# led_2835_driver_circle_10X10cm.net
KiCad netlist of a schematic drawn in Altium Designer
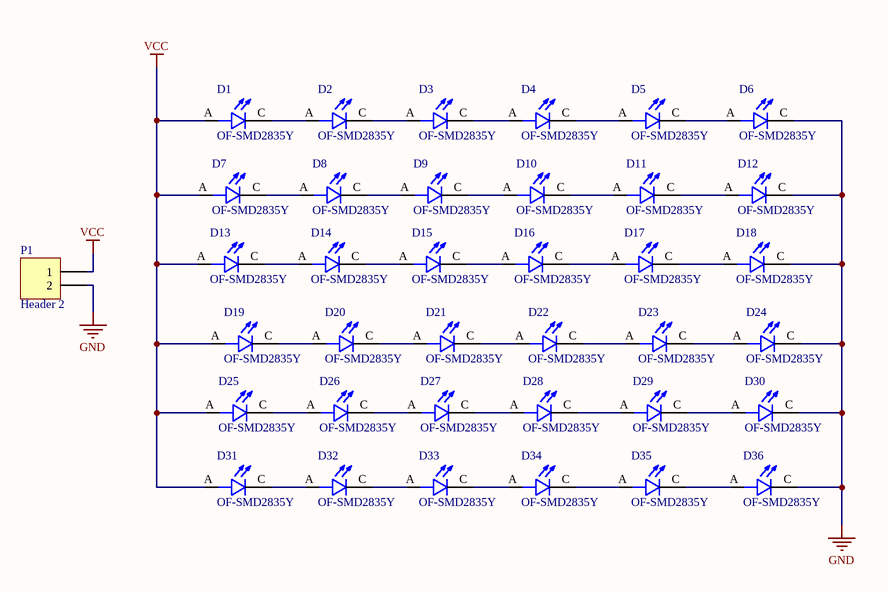
[diagram p0: led_2835_driver_circle_10X10cm.SchDoc]

(export (version "E")
  (design (tool "Eeschema 10.0.6"))
  (components
    (comp (ref "D1")
      (value "OF-SMD2835Y")
      (footprint "LED_OF-SMD2835Y")
      (description "LED; SMD; 2835, PLCC2; yellow; 2200-2800mcd; 2.8x3.5x0.75mm; 120Â°")
      (libsource (lib "") (part "OF-SMD2835Y_1"))
    )
    (comp (ref "D2")
      (value "OF-SMD2835Y")
      (footprint "LED_OF-SMD2835Y")
      (description "LED; SMD; 2835, PLCC2; yellow; 2200-2800mcd; 2.8x3.5x0.75mm; 120Â°")
      (libsource (lib "OF-SMD2835Y") (part "OF-SMD2835Y"))
    )
    (comp (ref "D3")
      (value "OF-SMD2835Y")
      (footprint "LED_OF-SMD2835Y")
      (description "LED; SMD; 2835, PLCC2; yellow; 2200-2800mcd; 2.8x3.5x0.75mm; 120Â°")
      (libsource (lib "OF-SMD2835Y") (part "OF-SMD2835Y"))
    )
    (comp (ref "D4")
      (value "OF-SMD2835Y")
      (footprint "LED_OF-SMD2835Y")
      (description "LED; SMD; 2835, PLCC2; yellow; 2200-2800mcd; 2.8x3.5x0.75mm; 120Â°")
      (libsource (lib "OF-SMD2835Y") (part "OF-SMD2835Y"))
    )
    (comp (ref "D5")
      (value "OF-SMD2835Y")
      (footprint "LED_OF-SMD2835Y")
      (description "LED; SMD; 2835, PLCC2; yellow; 2200-2800mcd; 2.8x3.5x0.75mm; 120Â°")
      (libsource (lib "OF-SMD2835Y") (part "OF-SMD2835Y"))
    )
    (comp (ref "D6")
      (value "OF-SMD2835Y")
      (footprint "LED_OF-SMD2835Y")
      (description "LED; SMD; 2835, PLCC2; yellow; 2200-2800mcd; 2.8x3.5x0.75mm; 120Â°")
      (libsource (lib "OF-SMD2835Y") (part "OF-SMD2835Y"))
    )
    (comp (ref "D7")
      (value "OF-SMD2835Y")
      (footprint "LED_OF-SMD2835Y")
      (description "LED; SMD; 2835, PLCC2; yellow; 2200-2800mcd; 2.8x3.5x0.75mm; 120Â°")
      (libsource (lib "") (part "OF-SMD2835Y_1"))
    )
    (comp (ref "D8")
      (value "OF-SMD2835Y")
      (footprint "LED_OF-SMD2835Y")
      (description "LED; SMD; 2835, PLCC2; yellow; 2200-2800mcd; 2.8x3.5x0.75mm; 120Â°")
      (libsource (lib "OF-SMD2835Y") (part "OF-SMD2835Y"))
    )
    (comp (ref "D9")
      (value "OF-SMD2835Y")
      (footprint "LED_OF-SMD2835Y")
      (description "LED; SMD; 2835, PLCC2; yellow; 2200-2800mcd; 2.8x3.5x0.75mm; 120Â°")
      (libsource (lib "OF-SMD2835Y") (part "OF-SMD2835Y"))
    )
    (comp (ref "D10")
      (value "OF-SMD2835Y")
      (footprint "LED_OF-SMD2835Y")
      (description "LED; SMD; 2835, PLCC2; yellow; 2200-2800mcd; 2.8x3.5x0.75mm; 120Â°")
      (libsource (lib "OF-SMD2835Y") (part "OF-SMD2835Y"))
    )
    (comp (ref "D11")
      (value "OF-SMD2835Y")
      (footprint "LED_OF-SMD2835Y")
      (description "LED; SMD; 2835, PLCC2; yellow; 2200-2800mcd; 2.8x3.5x0.75mm; 120Â°")
      (libsource (lib "OF-SMD2835Y") (part "OF-SMD2835Y"))
    )
    (comp (ref "D12")
      (value "OF-SMD2835Y")
      (footprint "LED_OF-SMD2835Y")
      (description "LED; SMD; 2835, PLCC2; yellow; 2200-2800mcd; 2.8x3.5x0.75mm; 120Â°")
      (libsource (lib "OF-SMD2835Y") (part "OF-SMD2835Y"))
    )
    (comp (ref "D13")
      (value "OF-SMD2835Y")
      (footprint "LED_OF-SMD2835Y")
      (description "LED; SMD; 2835, PLCC2; yellow; 2200-2800mcd; 2.8x3.5x0.75mm; 120Â°")
      (libsource (lib "") (part "OF-SMD2835Y_1"))
    )
    (comp (ref "D14")
      (value "OF-SMD2835Y")
      (footprint "LED_OF-SMD2835Y")
      (description "LED; SMD; 2835, PLCC2; yellow; 2200-2800mcd; 2.8x3.5x0.75mm; 120Â°")
      (libsource (lib "") (part "OF-SMD2835Y_1"))
    )
    (comp (ref "D15")
      (value "OF-SMD2835Y")
      (footprint "LED_OF-SMD2835Y")
      (description "LED; SMD; 2835, PLCC2; yellow; 2200-2800mcd; 2.8x3.5x0.75mm; 120Â°")
      (libsource (lib "OF-SMD2835Y") (part "OF-SMD2835Y"))
    )
    (comp (ref "D16")
      (value "OF-SMD2835Y")
      (footprint "LED_OF-SMD2835Y")
      (description "LED; SMD; 2835, PLCC2; yellow; 2200-2800mcd; 2.8x3.5x0.75mm; 120Â°")
      (libsource (lib "OF-SMD2835Y") (part "OF-SMD2835Y"))
    )
    (comp (ref "D17")
      (value "OF-SMD2835Y")
      (footprint "LED_OF-SMD2835Y")
      (description "LED; SMD; 2835, PLCC2; yellow; 2200-2800mcd; 2.8x3.5x0.75mm; 120Â°")
      (libsource (lib "OF-SMD2835Y") (part "OF-SMD2835Y"))
    )
    (comp (ref "D18")
      (value "OF-SMD2835Y")
      (footprint "LED_OF-SMD2835Y")
      (description "LED; SMD; 2835, PLCC2; yellow; 2200-2800mcd; 2.8x3.5x0.75mm; 120Â°")
      (libsource (lib "OF-SMD2835Y") (part "OF-SMD2835Y"))
    )
    (comp (ref "D19")
      (value "OF-SMD2835Y")
      (footprint "LED_OF-SMD2835Y")
      (description "LED; SMD; 2835, PLCC2; yellow; 2200-2800mcd; 2.8x3.5x0.75mm; 120Â°")
      (libsource (lib "") (part "OF-SMD2835Y_1"))
    )
    (comp (ref "D20")
      (value "OF-SMD2835Y")
      (footprint "LED_OF-SMD2835Y")
      (description "LED; SMD; 2835, PLCC2; yellow; 2200-2800mcd; 2.8x3.5x0.75mm; 120Â°")
      (libsource (lib "OF-SMD2835Y") (part "OF-SMD2835Y"))
    )
    (comp (ref "D21")
      (value "OF-SMD2835Y")
      (footprint "LED_OF-SMD2835Y")
      (description "LED; SMD; 2835, PLCC2; yellow; 2200-2800mcd; 2.8x3.5x0.75mm; 120Â°")
      (libsource (lib "OF-SMD2835Y") (part "OF-SMD2835Y"))
    )
    (comp (ref "D22")
      (value "OF-SMD2835Y")
      (footprint "LED_OF-SMD2835Y")
      (description "LED; SMD; 2835, PLCC2; yellow; 2200-2800mcd; 2.8x3.5x0.75mm; 120Â°")
      (libsource (lib "OF-SMD2835Y") (part "OF-SMD2835Y"))
    )
    (comp (ref "D23")
      (value "OF-SMD2835Y")
      (footprint "LED_OF-SMD2835Y")
      (description "LED; SMD; 2835, PLCC2; yellow; 2200-2800mcd; 2.8x3.5x0.75mm; 120Â°")
      (libsource (lib "OF-SMD2835Y") (part "OF-SMD2835Y"))
    )
    (comp (ref "D24")
      (value "OF-SMD2835Y")
      (footprint "LED_OF-SMD2835Y")
      (description "LED; SMD; 2835, PLCC2; yellow; 2200-2800mcd; 2.8x3.5x0.75mm; 120Â°")
      (libsource (lib "OF-SMD2835Y") (part "OF-SMD2835Y"))
    )
    (comp (ref "D25")
      (value "OF-SMD2835Y")
      (footprint "LED_OF-SMD2835Y")
      (description "LED; SMD; 2835, PLCC2; yellow; 2200-2800mcd; 2.8x3.5x0.75mm; 120Â°")
      (libsource (lib "") (part "OF-SMD2835Y_1"))
    )
    (comp (ref "D26")
      (value "OF-SMD2835Y")
      (footprint "LED_OF-SMD2835Y")
      (description "LED; SMD; 2835, PLCC2; yellow; 2200-2800mcd; 2.8x3.5x0.75mm; 120Â°")
      (libsource (lib "OF-SMD2835Y") (part "OF-SMD2835Y"))
    )
    (comp (ref "D27")
      (value "OF-SMD2835Y")
      (footprint "LED_OF-SMD2835Y")
      (description "LED; SMD; 2835, PLCC2; yellow; 2200-2800mcd; 2.8x3.5x0.75mm; 120Â°")
      (libsource (lib "OF-SMD2835Y") (part "OF-SMD2835Y"))
    )
    (comp (ref "D28")
      (value "OF-SMD2835Y")
      (footprint "LED_OF-SMD2835Y")
      (description "LED; SMD; 2835, PLCC2; yellow; 2200-2800mcd; 2.8x3.5x0.75mm; 120Â°")
      (libsource (lib "OF-SMD2835Y") (part "OF-SMD2835Y"))
    )
    (comp (ref "D29")
      (value "OF-SMD2835Y")
      (footprint "LED_OF-SMD2835Y")
      (description "LED; SMD; 2835, PLCC2; yellow; 2200-2800mcd; 2.8x3.5x0.75mm; 120Â°")
      (libsource (lib "OF-SMD2835Y") (part "OF-SMD2835Y"))
    )
    (comp (ref "D30")
      (value "OF-SMD2835Y")
      (footprint "LED_OF-SMD2835Y")
      (description "LED; SMD; 2835, PLCC2; yellow; 2200-2800mcd; 2.8x3.5x0.75mm; 120Â°")
      (libsource (lib "OF-SMD2835Y") (part "OF-SMD2835Y"))
    )
    (comp (ref "D31")
      (value "OF-SMD2835Y")
      (footprint "LED_OF-SMD2835Y")
      (description "LED; SMD; 2835, PLCC2; yellow; 2200-2800mcd; 2.8x3.5x0.75mm; 120Â°")
      (libsource (lib "") (part "OF-SMD2835Y_1"))
    )
    (comp (ref "D32")
      (value "OF-SMD2835Y")
      (footprint "LED_OF-SMD2835Y")
      (description "LED; SMD; 2835, PLCC2; yellow; 2200-2800mcd; 2.8x3.5x0.75mm; 120Â°")
      (libsource (lib "OF-SMD2835Y") (part "OF-SMD2835Y"))
    )
    (comp (ref "D33")
      (value "OF-SMD2835Y")
      (footprint "LED_OF-SMD2835Y")
      (description "LED; SMD; 2835, PLCC2; yellow; 2200-2800mcd; 2.8x3.5x0.75mm; 120Â°")
      (libsource (lib "OF-SMD2835Y") (part "OF-SMD2835Y"))
    )
    (comp (ref "D34")
      (value "OF-SMD2835Y")
      (footprint "LED_OF-SMD2835Y")
      (description "LED; SMD; 2835, PLCC2; yellow; 2200-2800mcd; 2.8x3.5x0.75mm; 120Â°")
      (libsource (lib "OF-SMD2835Y") (part "OF-SMD2835Y"))
    )
    (comp (ref "D35")
      (value "OF-SMD2835Y")
      (footprint "LED_OF-SMD2835Y")
      (description "LED; SMD; 2835, PLCC2; yellow; 2200-2800mcd; 2.8x3.5x0.75mm; 120Â°")
      (libsource (lib "OF-SMD2835Y") (part "OF-SMD2835Y"))
    )
    (comp (ref "D36")
      (value "OF-SMD2835Y")
      (footprint "LED_OF-SMD2835Y")
      (description "LED; SMD; 2835, PLCC2; yellow; 2200-2800mcd; 2.8x3.5x0.75mm; 120Â°")
      (libsource (lib "OF-SMD2835Y") (part "OF-SMD2835Y"))
    )
    (comp (ref "P1")
      (value "Header 2")
      (footprint "HDR1X2_SMD")
      (description "Header, 2-Pin")
      (fields (field (name "PUBLISHER") "Altium Limited"))
      (libsource (lib "Miscellaneous Connectors") (part "Header 2"))
    )
  )
  (nets
    (net (code "1") (name "GND") (class "Default")
      (node (ref "D12") (pin "C") (pinfunction "C_C") (pintype "passive"))
      (node (ref "D18") (pin "C") (pinfunction "C_C") (pintype "passive"))
      (node (ref "D24") (pin "C") (pinfunction "C_C") (pintype "passive"))
      (node (ref "D30") (pin "C") (pinfunction "C_C") (pintype "passive"))
      (node (ref "D36") (pin "C") (pinfunction "C_C") (pintype "passive"))
      (node (ref "D6") (pin "C") (pinfunction "C_C") (pintype "passive"))
      (node (ref "P1") (pin "2") (pinfunction "2_2") (pintype "passive"))
    )
    (net (code "2") (name "Net-(D1-PadC)") (class "Default")
      (node (ref "D1") (pin "C") (pinfunction "C_C") (pintype "passive"))
      (node (ref "D2") (pin "A") (pinfunction "A_A") (pintype "passive"))
    )
    (net (code "3") (name "Net-(D2-PadC)") (class "Default")
      (node (ref "D2") (pin "C") (pinfunction "C_C") (pintype "passive"))
      (node (ref "D3") (pin "A") (pinfunction "A_A") (pintype "passive"))
    )
    (net (code "4") (name "Net-(D3-PadC)") (class "Default")
      (node (ref "D3") (pin "C") (pinfunction "C_C") (pintype "passive"))
      (node (ref "D4") (pin "A") (pinfunction "A_A") (pintype "passive"))
    )
    (net (code "5") (name "Net-(D4-PadC)") (class "Default")
      (node (ref "D4") (pin "C") (pinfunction "C_C") (pintype "passive"))
      (node (ref "D5") (pin "A") (pinfunction "A_A") (pintype "passive"))
    )
    (net (code "6") (name "Net-(D5-PadC)") (class "Default")
      (node (ref "D5") (pin "C") (pinfunction "C_C") (pintype "passive"))
      (node (ref "D6") (pin "A") (pinfunction "A_A") (pintype "passive"))
    )
    (net (code "7") (name "Net-(D7-PadC)") (class "Default")
      (node (ref "D7") (pin "C") (pinfunction "C_C") (pintype "passive"))
      (node (ref "D8") (pin "A") (pinfunction "A_A") (pintype "passive"))
    )
    (net (code "8") (name "Net-(D8-PadC)") (class "Default")
      (node (ref "D8") (pin "C") (pinfunction "C_C") (pintype "passive"))
      (node (ref "D9") (pin "A") (pinfunction "A_A") (pintype "passive"))
    )
    (net (code "9") (name "Net-(D10-PadA)") (class "Default")
      (node (ref "D10") (pin "A") (pinfunction "A_A") (pintype "passive"))
      (node (ref "D9") (pin "C") (pinfunction "C_C") (pintype "passive"))
    )
    (net (code "10") (name "Net-(D10-PadC)") (class "Default")
      (node (ref "D10") (pin "C") (pinfunction "C_C") (pintype "passive"))
      (node (ref "D11") (pin "A") (pinfunction "A_A") (pintype "passive"))
    )
    (net (code "11") (name "Net-(D11-PadC)") (class "Default")
      (node (ref "D11") (pin "C") (pinfunction "C_C") (pintype "passive"))
      (node (ref "D12") (pin "A") (pinfunction "A_A") (pintype "passive"))
    )
    (net (code "12") (name "Net-(D13-PadC)") (class "Default")
      (node (ref "D13") (pin "C") (pinfunction "C_C") (pintype "passive"))
      (node (ref "D14") (pin "A") (pinfunction "A_A") (pintype "passive"))
    )
    (net (code "13") (name "Net-(D14-PadC)") (class "Default")
      (node (ref "D14") (pin "C") (pinfunction "C_C") (pintype "passive"))
      (node (ref "D15") (pin "A") (pinfunction "A_A") (pintype "passive"))
    )
    (net (code "14") (name "Net-(D15-PadC)") (class "Default")
      (node (ref "D15") (pin "C") (pinfunction "C_C") (pintype "passive"))
      (node (ref "D16") (pin "A") (pinfunction "A_A") (pintype "passive"))
    )
    (net (code "15") (name "Net-(D16-PadC)") (class "Default")
      (node (ref "D16") (pin "C") (pinfunction "C_C") (pintype "passive"))
      (node (ref "D17") (pin "A") (pinfunction "A_A") (pintype "passive"))
    )
    (net (code "16") (name "Net-(D17-PadC)") (class "Default")
      (node (ref "D17") (pin "C") (pinfunction "C_C") (pintype "passive"))
      (node (ref "D18") (pin "A") (pinfunction "A_A") (pintype "passive"))
    )
    (net (code "17") (name "Net-(D19-PadC)") (class "Default")
      (node (ref "D19") (pin "C") (pinfunction "C_C") (pintype "passive"))
      (node (ref "D20") (pin "A") (pinfunction "A_A") (pintype "passive"))
    )
    (net (code "18") (name "Net-(D20-PadC)") (class "Default")
      (node (ref "D20") (pin "C") (pinfunction "C_C") (pintype "passive"))
      (node (ref "D21") (pin "A") (pinfunction "A_A") (pintype "passive"))
    )
    (net (code "19") (name "Net-(D21-PadC)") (class "Default")
      (node (ref "D21") (pin "C") (pinfunction "C_C") (pintype "passive"))
      (node (ref "D22") (pin "A") (pinfunction "A_A") (pintype "passive"))
    )
    (net (code "20") (name "Net-(D22-PadC)") (class "Default")
      (node (ref "D22") (pin "C") (pinfunction "C_C") (pintype "passive"))
      (node (ref "D23") (pin "A") (pinfunction "A_A") (pintype "passive"))
    )
    (net (code "21") (name "Net-(D23-PadC)") (class "Default")
      (node (ref "D23") (pin "C") (pinfunction "C_C") (pintype "passive"))
      (node (ref "D24") (pin "A") (pinfunction "A_A") (pintype "passive"))
    )
    (net (code "22") (name "Net-(D25-PadC)") (class "Default")
      (node (ref "D25") (pin "C") (pinfunction "C_C") (pintype "passive"))
      (node (ref "D26") (pin "A") (pinfunction "A_A") (pintype "passive"))
    )
    (net (code "23") (name "Net-(D26-PadC)") (class "Default")
      (node (ref "D26") (pin "C") (pinfunction "C_C") (pintype "passive"))
      (node (ref "D27") (pin "A") (pinfunction "A_A") (pintype "passive"))
    )
    (net (code "24") (name "Net-(D27-PadC)") (class "Default")
      (node (ref "D27") (pin "C") (pinfunction "C_C") (pintype "passive"))
      (node (ref "D28") (pin "A") (pinfunction "A_A") (pintype "passive"))
    )
    (net (code "25") (name "Net-(D28-PadC)") (class "Default")
      (node (ref "D28") (pin "C") (pinfunction "C_C") (pintype "passive"))
      (node (ref "D29") (pin "A") (pinfunction "A_A") (pintype "passive"))
    )
    (net (code "26") (name "Net-(D29-PadC)") (class "Default")
      (node (ref "D29") (pin "C") (pinfunction "C_C") (pintype "passive"))
      (node (ref "D30") (pin "A") (pinfunction "A_A") (pintype "passive"))
    )
    (net (code "27") (name "Net-(D31-PadC)") (class "Default")
      (node (ref "D31") (pin "C") (pinfunction "C_C") (pintype "passive"))
      (node (ref "D32") (pin "A") (pinfunction "A_A") (pintype "passive"))
    )
    (net (code "28") (name "Net-(D32-PadC)") (class "Default")
      (node (ref "D32") (pin "C") (pinfunction "C_C") (pintype "passive"))
      (node (ref "D33") (pin "A") (pinfunction "A_A") (pintype "passive"))
    )
    (net (code "29") (name "Net-(D33-PadC)") (class "Default")
      (node (ref "D33") (pin "C") (pinfunction "C_C") (pintype "passive"))
      (node (ref "D34") (pin "A") (pinfunction "A_A") (pintype "passive"))
    )
    (net (code "30") (name "Net-(D34-PadC)") (class "Default")
      (node (ref "D34") (pin "C") (pinfunction "C_C") (pintype "passive"))
      (node (ref "D35") (pin "A") (pinfunction "A_A") (pintype "passive"))
    )
    (net (code "31") (name "Net-(D35-PadC)") (class "Default")
      (node (ref "D35") (pin "C") (pinfunction "C_C") (pintype "passive"))
      (node (ref "D36") (pin "A") (pinfunction "A_A") (pintype "passive"))
    )
    (net (code "32") (name "VCC") (class "Default")
      (node (ref "D1") (pin "A") (pinfunction "A_A") (pintype "passive"))
      (node (ref "D13") (pin "A") (pinfunction "A_A") (pintype "passive"))
      (node (ref "D19") (pin "A") (pinfunction "A_A") (pintype "passive"))
      (node (ref "D25") (pin "A") (pinfunction "A_A") (pintype "passive"))
      (node (ref "D31") (pin "A") (pinfunction "A_A") (pintype "passive"))
      (node (ref "D7") (pin "A") (pinfunction "A_A") (pintype "passive"))
      (node (ref "P1") (pin "1") (pinfunction "1_1") (pintype "passive"))
    )
  )
)
